# Sheet0_Top.net
KiCad netlist of a schematic drawn in Altium Designer
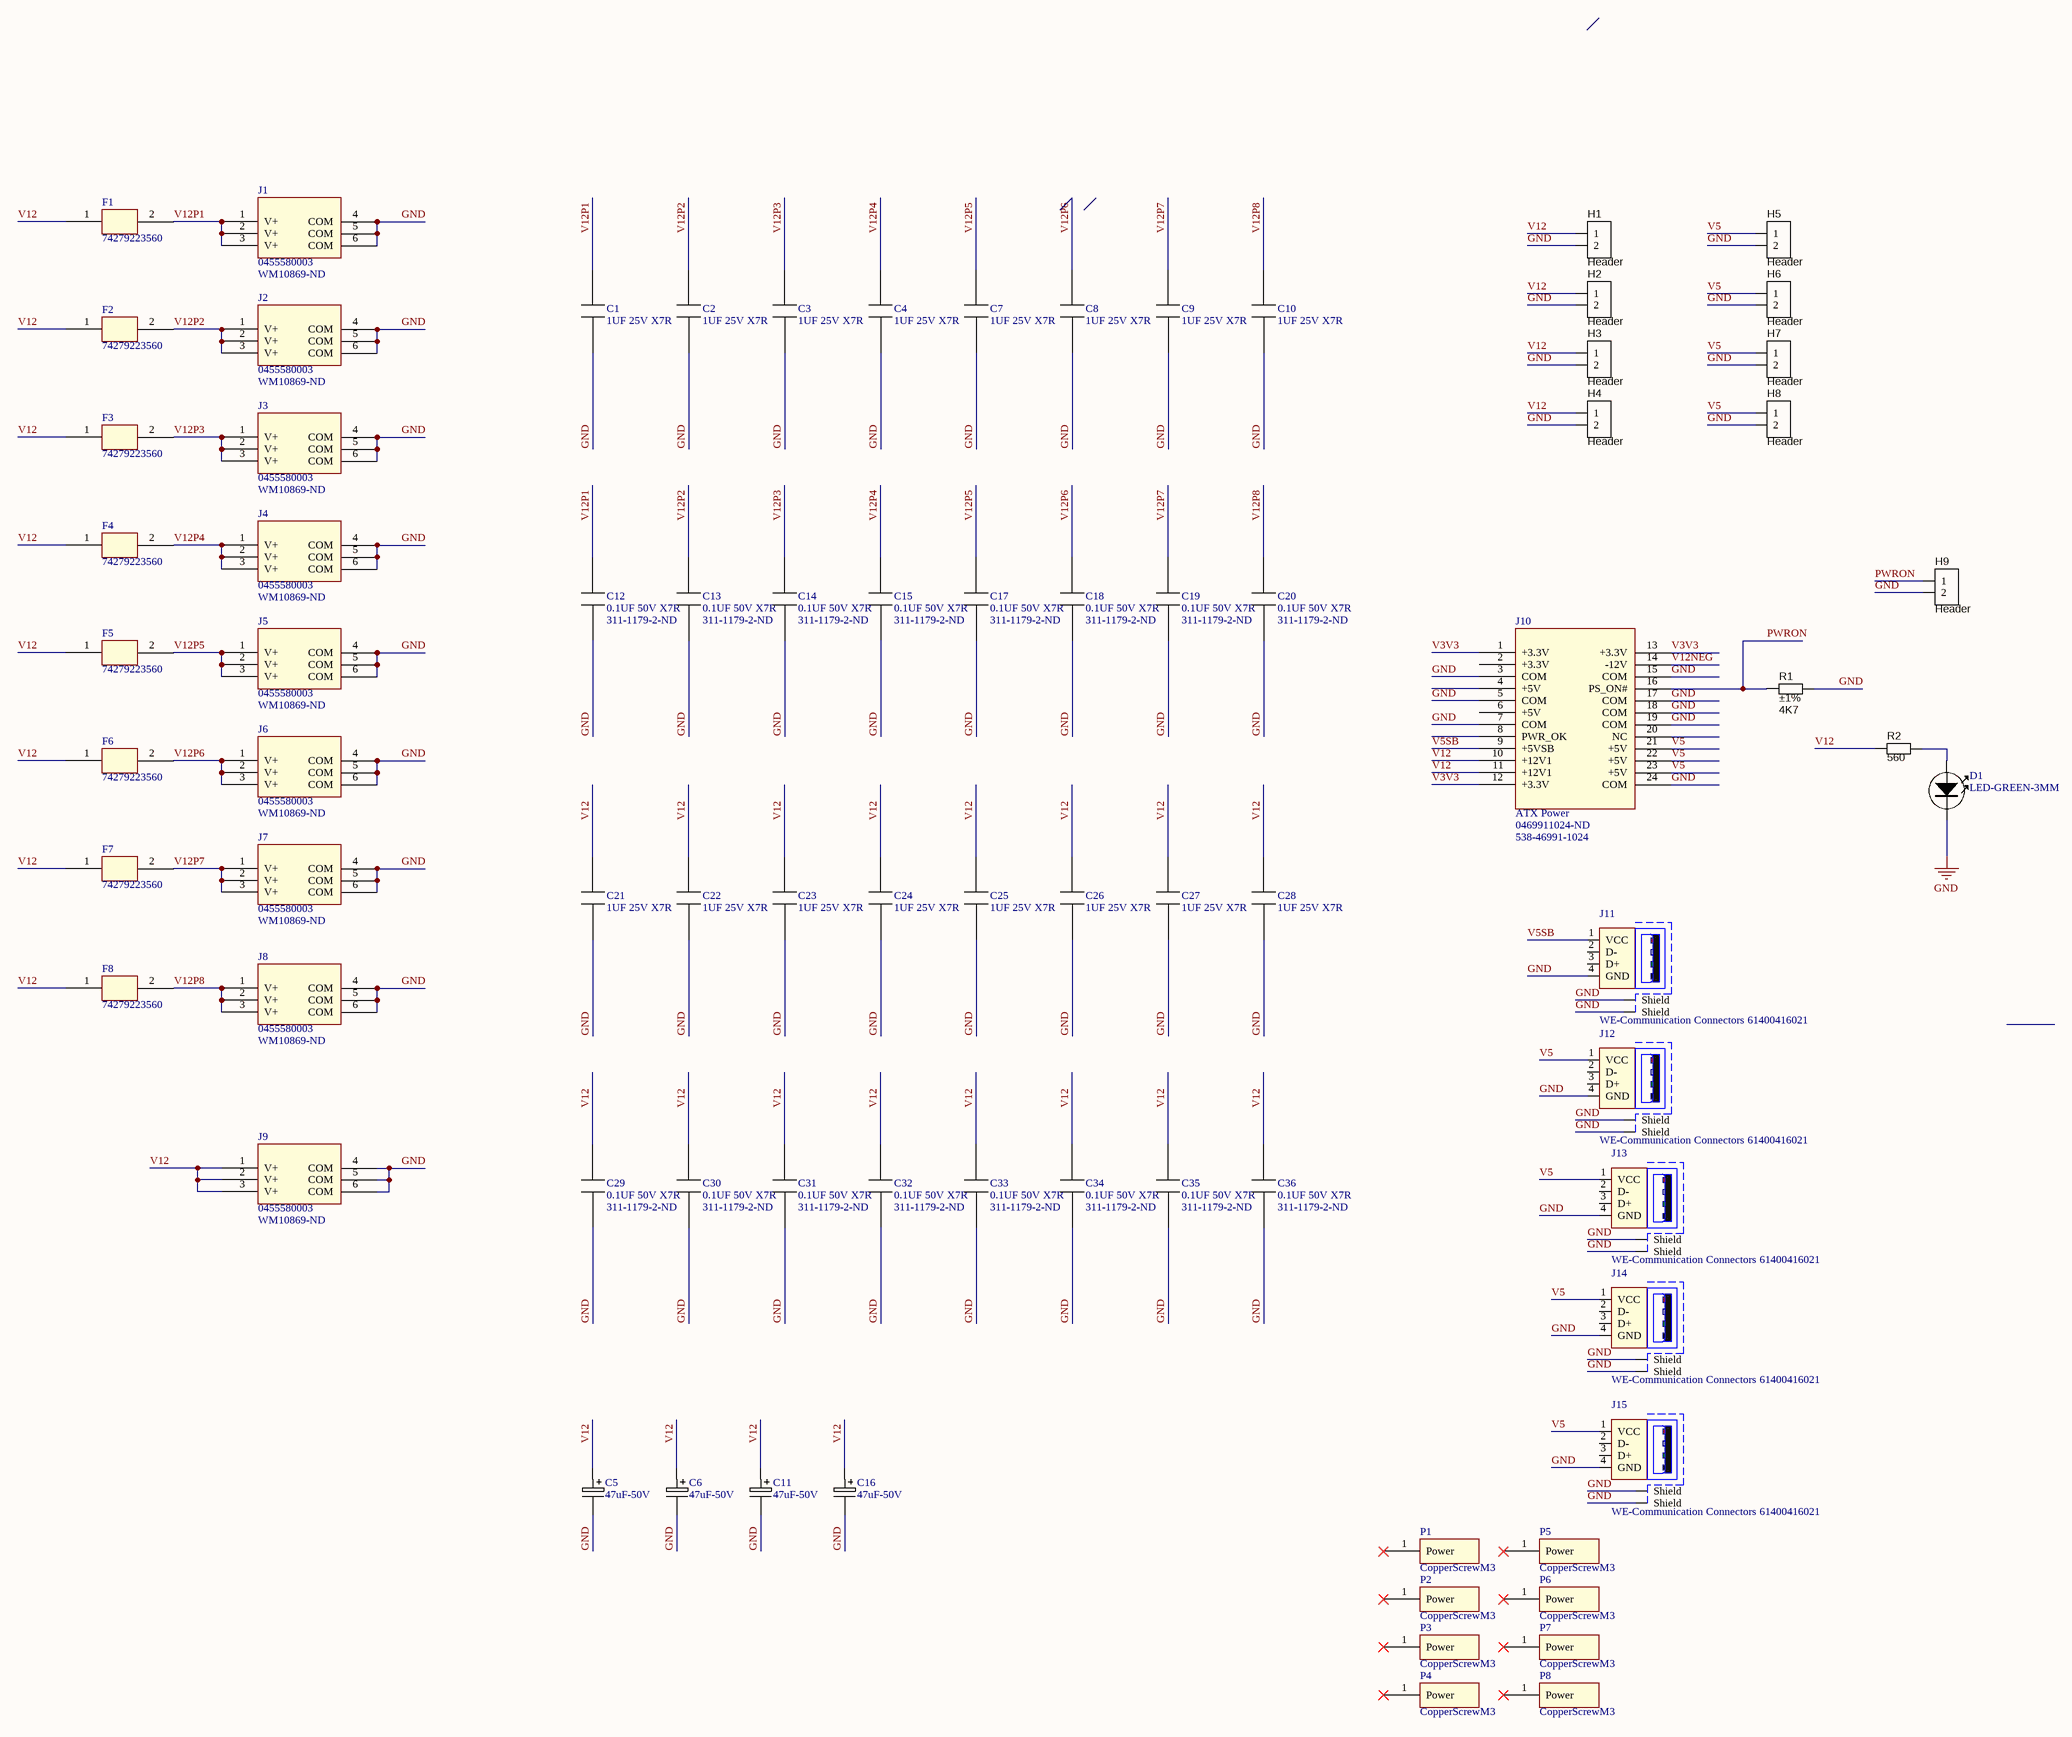
[diagram p0: Sheet0_Top.SchDoc]

(export (version "E")
  (design (tool "Eeschema 10.0.6"))
  (components
    (comp (ref "C1")
      (value "1UF 25V X7R")
      (footprint "C1206YageoX7R")
      (description "CAP CER 1UF 25V X7R 1206 Yageo CC1206KKX7R8BB105")
      (libsource (lib "servo") (part "CC1206KKX7R8BB105"))
    )
    (comp (ref "C2")
      (value "1UF 25V X7R")
      (footprint "C1206YageoX7R")
      (description "CAP CER 1UF 25V X7R 1206 Yageo CC1206KKX7R8BB105")
      (libsource (lib "servo") (part "CC1206KKX7R8BB105"))
    )
    (comp (ref "C3")
      (value "1UF 25V X7R")
      (footprint "C1206YageoX7R")
      (description "CAP CER 1UF 25V X7R 1206 Yageo CC1206KKX7R8BB105")
      (libsource (lib "servo") (part "CC1206KKX7R8BB105"))
    )
    (comp (ref "C4")
      (value "1UF 25V X7R")
      (footprint "C1206YageoX7R")
      (description "CAP CER 1UF 25V X7R 1206 Yageo CC1206KKX7R8BB105")
      (libsource (lib "servo") (part "CC1206KKX7R8BB105"))
    )
    (comp (ref "C5")
      (value "47uF-50V")
      (footprint "PANACAP-E-GENERIC")
      (description "GENERIC CAPACITOR POLARISED")
      (libsource (lib "SMD Capacitors Electrolytic") (part "PANACAP-47UF-50V-FK"))
    )
    (comp (ref "C6")
      (value "47uF-50V")
      (footprint "PANACAP-E-GENERIC")
      (description "GENERIC CAPACITOR POLARISED")
      (libsource (lib "SMD Capacitors Electrolytic") (part "PANACAP-47UF-50V-FK"))
    )
    (comp (ref "C7")
      (value "1UF 25V X7R")
      (footprint "C1206YageoX7R")
      (description "CAP CER 1UF 25V X7R 1206 Yageo CC1206KKX7R8BB105")
      (libsource (lib "servo") (part "CC1206KKX7R8BB105"))
    )
    (comp (ref "C8")
      (value "1UF 25V X7R")
      (footprint "C1206YageoX7R")
      (description "CAP CER 1UF 25V X7R 1206 Yageo CC1206KKX7R8BB105")
      (libsource (lib "servo") (part "CC1206KKX7R8BB105"))
    )
    (comp (ref "C9")
      (value "1UF 25V X7R")
      (footprint "C1206YageoX7R")
      (description "CAP CER 1UF 25V X7R 1206 Yageo CC1206KKX7R8BB105")
      (libsource (lib "servo") (part "CC1206KKX7R8BB105"))
    )
    (comp (ref "C10")
      (value "1UF 25V X7R")
      (footprint "C1206YageoX7R")
      (description "CAP CER 1UF 25V X7R 1206 Yageo CC1206KKX7R8BB105")
      (libsource (lib "servo") (part "CC1206KKX7R8BB105"))
    )
    (comp (ref "C11")
      (value "47uF-50V")
      (footprint "PANACAP-E-GENERIC")
      (description "GENERIC CAPACITOR POLARISED")
      (libsource (lib "SMD Capacitors Electrolytic") (part "PANACAP-47UF-50V-FK"))
    )
    (comp (ref "C12")
      (value "0.1UF 50V X7R")
      (footprint "C1206YageoX7R")
      (description "CAP CER 0.1UF 50V X7R 1206 YAGEO CC1206KRX7R9BB104")
      (fields (field (name "SUPPLIER PART NUMBER 1") "311-1179-2-ND"))
      (libsource (lib "servo") (part "CC1206KRX7R9BB104"))
    )
    (comp (ref "C13")
      (value "0.1UF 50V X7R")
      (footprint "C1206YageoX7R")
      (description "CAP CER 0.1UF 50V X7R 1206 YAGEO CC1206KRX7R9BB104")
      (fields (field (name "SUPPLIER PART NUMBER 1") "311-1179-2-ND"))
      (libsource (lib "servo") (part "CC1206KRX7R9BB104"))
    )
    (comp (ref "C14")
      (value "0.1UF 50V X7R")
      (footprint "C1206YageoX7R")
      (description "CAP CER 0.1UF 50V X7R 1206 YAGEO CC1206KRX7R9BB104")
      (fields (field (name "SUPPLIER PART NUMBER 1") "311-1179-2-ND"))
      (libsource (lib "servo") (part "CC1206KRX7R9BB104"))
    )
    (comp (ref "C15")
      (value "0.1UF 50V X7R")
      (footprint "C1206YageoX7R")
      (description "CAP CER 0.1UF 50V X7R 1206 YAGEO CC1206KRX7R9BB104")
      (fields (field (name "SUPPLIER PART NUMBER 1") "311-1179-2-ND"))
      (libsource (lib "servo") (part "CC1206KRX7R9BB104"))
    )
    (comp (ref "C16")
      (value "47uF-50V")
      (footprint "PANACAP-E-GENERIC")
      (description "GENERIC CAPACITOR POLARISED")
      (libsource (lib "SMD Capacitors Electrolytic") (part "PANACAP-47UF-50V-FK"))
    )
    (comp (ref "C17")
      (value "0.1UF 50V X7R")
      (footprint "C1206YageoX7R")
      (description "CAP CER 0.1UF 50V X7R 1206 YAGEO CC1206KRX7R9BB104")
      (fields (field (name "SUPPLIER PART NUMBER 1") "311-1179-2-ND"))
      (libsource (lib "servo") (part "CC1206KRX7R9BB104"))
    )
    (comp (ref "C18")
      (value "0.1UF 50V X7R")
      (footprint "C1206YageoX7R")
      (description "CAP CER 0.1UF 50V X7R 1206 YAGEO CC1206KRX7R9BB104")
      (fields (field (name "SUPPLIER PART NUMBER 1") "311-1179-2-ND"))
      (libsource (lib "servo") (part "CC1206KRX7R9BB104"))
    )
    (comp (ref "C19")
      (value "0.1UF 50V X7R")
      (footprint "C1206YageoX7R")
      (description "CAP CER 0.1UF 50V X7R 1206 YAGEO CC1206KRX7R9BB104")
      (fields (field (name "SUPPLIER PART NUMBER 1") "311-1179-2-ND"))
      (libsource (lib "servo") (part "CC1206KRX7R9BB104"))
    )
    (comp (ref "C20")
      (value "0.1UF 50V X7R")
      (footprint "C1206YageoX7R")
      (description "CAP CER 0.1UF 50V X7R 1206 YAGEO CC1206KRX7R9BB104")
      (fields (field (name "SUPPLIER PART NUMBER 1") "311-1179-2-ND"))
      (libsource (lib "servo") (part "CC1206KRX7R9BB104"))
    )
    (comp (ref "C21")
      (value "1UF 25V X7R")
      (footprint "C1206YageoX7R")
      (description "CAP CER 1UF 25V X7R 1206 Yageo CC1206KKX7R8BB105")
      (libsource (lib "servo") (part "CC1206KKX7R8BB105"))
    )
    (comp (ref "C22")
      (value "1UF 25V X7R")
      (footprint "C1206YageoX7R")
      (description "CAP CER 1UF 25V X7R 1206 Yageo CC1206KKX7R8BB105")
      (libsource (lib "servo") (part "CC1206KKX7R8BB105"))
    )
    (comp (ref "C23")
      (value "1UF 25V X7R")
      (footprint "C1206YageoX7R")
      (description "CAP CER 1UF 25V X7R 1206 Yageo CC1206KKX7R8BB105")
      (libsource (lib "servo") (part "CC1206KKX7R8BB105"))
    )
    (comp (ref "C24")
      (value "1UF 25V X7R")
      (footprint "C1206YageoX7R")
      (description "CAP CER 1UF 25V X7R 1206 Yageo CC1206KKX7R8BB105")
      (libsource (lib "servo") (part "CC1206KKX7R8BB105"))
    )
    (comp (ref "C25")
      (value "1UF 25V X7R")
      (footprint "C1206YageoX7R")
      (description "CAP CER 1UF 25V X7R 1206 Yageo CC1206KKX7R8BB105")
      (libsource (lib "servo") (part "CC1206KKX7R8BB105"))
    )
    (comp (ref "C26")
      (value "1UF 25V X7R")
      (footprint "C1206YageoX7R")
      (description "CAP CER 1UF 25V X7R 1206 Yageo CC1206KKX7R8BB105")
      (libsource (lib "servo") (part "CC1206KKX7R8BB105"))
    )
    (comp (ref "C27")
      (value "1UF 25V X7R")
      (footprint "C1206YageoX7R")
      (description "CAP CER 1UF 25V X7R 1206 Yageo CC1206KKX7R8BB105")
      (libsource (lib "servo") (part "CC1206KKX7R8BB105"))
    )
    (comp (ref "C28")
      (value "1UF 25V X7R")
      (footprint "C1206YageoX7R")
      (description "CAP CER 1UF 25V X7R 1206 Yageo CC1206KKX7R8BB105")
      (libsource (lib "servo") (part "CC1206KKX7R8BB105"))
    )
    (comp (ref "C29")
      (value "0.1UF 50V X7R")
      (footprint "C1206YageoX7R")
      (description "CAP CER 0.1UF 50V X7R 1206 YAGEO CC1206KRX7R9BB104")
      (fields (field (name "SUPPLIER PART NUMBER 1") "311-1179-2-ND"))
      (libsource (lib "servo") (part "CC1206KRX7R9BB104"))
    )
    (comp (ref "C30")
      (value "0.1UF 50V X7R")
      (footprint "C1206YageoX7R")
      (description "CAP CER 0.1UF 50V X7R 1206 YAGEO CC1206KRX7R9BB104")
      (fields (field (name "SUPPLIER PART NUMBER 1") "311-1179-2-ND"))
      (libsource (lib "servo") (part "CC1206KRX7R9BB104"))
    )
    (comp (ref "C31")
      (value "0.1UF 50V X7R")
      (footprint "C1206YageoX7R")
      (description "CAP CER 0.1UF 50V X7R 1206 YAGEO CC1206KRX7R9BB104")
      (fields (field (name "SUPPLIER PART NUMBER 1") "311-1179-2-ND"))
      (libsource (lib "servo") (part "CC1206KRX7R9BB104"))
    )
    (comp (ref "C32")
      (value "0.1UF 50V X7R")
      (footprint "C1206YageoX7R")
      (description "CAP CER 0.1UF 50V X7R 1206 YAGEO CC1206KRX7R9BB104")
      (fields (field (name "SUPPLIER PART NUMBER 1") "311-1179-2-ND"))
      (libsource (lib "servo") (part "CC1206KRX7R9BB104"))
    )
    (comp (ref "C33")
      (value "0.1UF 50V X7R")
      (footprint "C1206YageoX7R")
      (description "CAP CER 0.1UF 50V X7R 1206 YAGEO CC1206KRX7R9BB104")
      (fields (field (name "SUPPLIER PART NUMBER 1") "311-1179-2-ND"))
      (libsource (lib "servo") (part "CC1206KRX7R9BB104"))
    )
    (comp (ref "C34")
      (value "0.1UF 50V X7R")
      (footprint "C1206YageoX7R")
      (description "CAP CER 0.1UF 50V X7R 1206 YAGEO CC1206KRX7R9BB104")
      (fields (field (name "SUPPLIER PART NUMBER 1") "311-1179-2-ND"))
      (libsource (lib "servo") (part "CC1206KRX7R9BB104"))
    )
    (comp (ref "C35")
      (value "0.1UF 50V X7R")
      (footprint "C1206YageoX7R")
      (description "CAP CER 0.1UF 50V X7R 1206 YAGEO CC1206KRX7R9BB104")
      (fields (field (name "SUPPLIER PART NUMBER 1") "311-1179-2-ND"))
      (libsource (lib "servo") (part "CC1206KRX7R9BB104"))
    )
    (comp (ref "C36")
      (value "0.1UF 50V X7R")
      (footprint "C1206YageoX7R")
      (description "CAP CER 0.1UF 50V X7R 1206 YAGEO CC1206KRX7R9BB104")
      (fields (field (name "SUPPLIER PART NUMBER 1") "311-1179-2-ND"))
      (libsource (lib "servo") (part "CC1206KRX7R9BB104"))
    )
    (comp (ref "D1")
      (value "LED-GREEN-3MM")
      (footprint "LED-3MM-GREEN")
      (libsource (lib "TH Optoelectronics") (part "LED-GREEN-3MM"))
    )
    (comp (ref "F1")
      (value "74279223560")
      (footprint "74279223560")
      (description "Wurth 74279223560 Ferrite Bead 4000 uohm 10Amps")
      (libsource (lib "pwr8") (part "74279223560"))
    )
    (comp (ref "F2")
      (value "74279223560")
      (footprint "74279223560")
      (description "Wurth 74279223560 Ferrite Bead 4000 uohm 10Amps")
      (libsource (lib "pwr8") (part "74279223560"))
    )
    (comp (ref "F3")
      (value "74279223560")
      (footprint "74279223560")
      (description "Wurth 74279223560 Ferrite Bead 4000 uohm 10Amps")
      (libsource (lib "pwr8") (part "74279223560"))
    )
    (comp (ref "F4")
      (value "74279223560")
      (footprint "74279223560")
      (description "Wurth 74279223560 Ferrite Bead 4000 uohm 10Amps")
      (libsource (lib "pwr8") (part "74279223560"))
    )
    (comp (ref "F5")
      (value "74279223560")
      (footprint "74279223560")
      (description "Wurth 74279223560 Ferrite Bead 4000 uohm 10Amps")
      (libsource (lib "pwr8") (part "74279223560"))
    )
    (comp (ref "F6")
      (value "74279223560")
      (footprint "74279223560")
      (description "Wurth 74279223560 Ferrite Bead 4000 uohm 10Amps")
      (libsource (lib "pwr8") (part "74279223560"))
    )
    (comp (ref "F7")
      (value "74279223560")
      (footprint "74279223560")
      (description "Wurth 74279223560 Ferrite Bead 4000 uohm 10Amps")
      (libsource (lib "pwr8") (part "74279223560"))
    )
    (comp (ref "F8")
      (value "74279223560")
      (footprint "74279223560")
      (description "Wurth 74279223560 Ferrite Bead 4000 uohm 10Amps")
      (libsource (lib "pwr8") (part "74279223560"))
    )
    (comp (ref "H1")
      (value "Header")
      (footprint "HDR_1x2_Offset")
      (description "Header, 2-pin")
      (libsource (lib "PBL - Connectors") (part "Header2P"))
    )
    (comp (ref "H2")
      (value "Header")
      (footprint "HDR_1x2_Offset")
      (description "Header, 2-pin")
      (libsource (lib "PBL - Connectors") (part "Header2P"))
    )
    (comp (ref "H3")
      (value "Header")
      (footprint "HDR_1x2_Offset")
      (description "Header, 2-pin")
      (libsource (lib "PBL - Connectors") (part "Header2P"))
    )
    (comp (ref "H4")
      (value "Header")
      (footprint "HDR_1x2_Offset")
      (description "Header, 2-pin")
      (libsource (lib "PBL - Connectors") (part "Header2P"))
    )
    (comp (ref "H5")
      (value "Header")
      (footprint "HDR_1x2_Offset")
      (description "Header, 2-pin")
      (libsource (lib "PBL - Connectors") (part "Header2P"))
    )
    (comp (ref "H6")
      (value "Header")
      (footprint "HDR_1x2_Offset")
      (description "Header, 2-pin")
      (libsource (lib "PBL - Connectors") (part "Header2P"))
    )
    (comp (ref "H7")
      (value "Header")
      (footprint "HDR_1x2_Offset")
      (description "Header, 2-pin")
      (libsource (lib "PBL - Connectors") (part "Header2P"))
    )
    (comp (ref "H8")
      (value "Header")
      (footprint "HDR_1x2_Offset")
      (description "Header, 2-pin")
      (libsource (lib "PBL - Connectors") (part "Header2P"))
    )
    (comp (ref "H9")
      (value "Header")
      (footprint "HDR_1x2_Offset")
      (description "Header, 2-pin")
      (libsource (lib "PBL - Connectors") (part "Header2P"))
    )
    (comp (ref "J1")
      (value "0455580003")
      (footprint "45558")
      (fields (field (name "SUPPLIER PART NUMBER 1") "WM10869-ND"))
      (libsource (lib "fastcar") (part "0455580003"))
    )
    (comp (ref "J2")
      (value "0455580003")
      (footprint "45558")
      (fields (field (name "SUPPLIER PART NUMBER 1") "WM10869-ND"))
      (libsource (lib "fastcar") (part "0455580003"))
    )
    (comp (ref "J3")
      (value "0455580003")
      (footprint "45558")
      (fields (field (name "SUPPLIER PART NUMBER 1") "WM10869-ND"))
      (libsource (lib "fastcar") (part "0455580003"))
    )
    (comp (ref "J4")
      (value "0455580003")
      (footprint "45558")
      (fields (field (name "SUPPLIER PART NUMBER 1") "WM10869-ND"))
      (libsource (lib "fastcar") (part "0455580003"))
    )
    (comp (ref "J5")
      (value "0455580003")
      (footprint "45558")
      (fields (field (name "SUPPLIER PART NUMBER 1") "WM10869-ND"))
      (libsource (lib "fastcar") (part "0455580003"))
    )
    (comp (ref "J6")
      (value "0455580003")
      (footprint "45558")
      (fields (field (name "SUPPLIER PART NUMBER 1") "WM10869-ND"))
      (libsource (lib "fastcar") (part "0455580003"))
    )
    (comp (ref "J7")
      (value "0455580003")
      (footprint "45558")
      (fields (field (name "SUPPLIER PART NUMBER 1") "WM10869-ND"))
      (libsource (lib "fastcar") (part "0455580003"))
    )
    (comp (ref "J8")
      (value "0455580003")
      (footprint "45558")
      (fields (field (name "SUPPLIER PART NUMBER 1") "WM10869-ND"))
      (libsource (lib "fastcar") (part "0455580003"))
    )
    (comp (ref "J9")
      (value "0455580003")
      (footprint "45558")
      (fields (field (name "SUPPLIER PART NUMBER 1") "WM10869-ND"))
      (libsource (lib "fastcar") (part "0455580003"))
    )
    (comp (ref "J10")
      (value "ATX Power")
      (footprint "46991-1024")
      (description "Mini-Fit JR LCP RA HDR NOPEG 24C")
      (fields
        (field (name "SUPPLIER PART NUMBER 1") "0469911024-ND")
        (field (name "SUPPLIER PART NUMBER 2") "538-46991-1024")
      )
      (libsource (lib "fastcar") (part "46991-2024"))
    )
    (comp (ref "J11")
      (value "WE-Communication Connectors 61400416021")
      (footprint "61400416021")
      (description "WR-COM USB RA Type A")
      (fields
        (field (name "MANUFACTURER") "Würth Elektronik eiSos GmbH")
        (field (name "PARTNO") "61400416021")
        (field (name "CREATED BY") "Karrer Zheng")
      )
      (libsource (lib "USB-Mini_USB-Micro_USB") (part "WE-Communication Connectors 61400416021"))
    )
    (comp (ref "J12")
      (value "WE-Communication Connectors 61400416021")
      (footprint "61400416021")
      (description "WR-COM USB RA Type A")
      (fields
        (field (name "MANUFACTURER") "Würth Elektronik eiSos GmbH")
        (field (name "PARTNO") "61400416021")
        (field (name "CREATED BY") "Karrer Zheng")
      )
      (libsource (lib "USB-Mini_USB-Micro_USB") (part "WE-Communication Connectors 61400416021"))
    )
    (comp (ref "J13")
      (value "WE-Communication Connectors 61400416021")
      (footprint "61400416021")
      (description "WR-COM USB RA Type A")
      (fields
        (field (name "MANUFACTURER") "Würth Elektronik eiSos GmbH")
        (field (name "PARTNO") "61400416021")
        (field (name "CREATED BY") "Karrer Zheng")
      )
      (libsource (lib "USB-Mini_USB-Micro_USB") (part "WE-Communication Connectors 61400416021"))
    )
    (comp (ref "J14")
      (value "WE-Communication Connectors 61400416021")
      (footprint "61400416021")
      (description "WR-COM USB RA Type A")
      (fields
        (field (name "MANUFACTURER") "Würth Elektronik eiSos GmbH")
        (field (name "PARTNO") "61400416021")
        (field (name "CREATED BY") "Karrer Zheng")
      )
      (libsource (lib "USB-Mini_USB-Micro_USB") (part "WE-Communication Connectors 61400416021"))
    )
    (comp (ref "J15")
      (value "WE-Communication Connectors 61400416021")
      (footprint "61400416021")
      (description "WR-COM USB RA Type A")
      (fields
        (field (name "MANUFACTURER") "Würth Elektronik eiSos GmbH")
        (field (name "PARTNO") "61400416021")
        (field (name "CREATED BY") "Karrer Zheng")
      )
      (libsource (lib "USB-Mini_USB-Micro_USB") (part "WE-Communication Connectors 61400416021"))
    )
    (comp (ref "P1")
      (value "CopperScrewM3")
      (footprint "M3Screw")
      (libsource (lib "fastcar") (part "CopperScrewM3"))
    )
    (comp (ref "P2")
      (value "CopperScrewM3")
      (footprint "M3Screw")
      (libsource (lib "fastcar") (part "CopperScrewM3"))
    )
    (comp (ref "P3")
      (value "CopperScrewM3")
      (footprint "M3Screw")
      (libsource (lib "fastcar") (part "CopperScrewM3"))
    )
    (comp (ref "P4")
      (value "CopperScrewM3")
      (footprint "M3Screw")
      (libsource (lib "fastcar") (part "CopperScrewM3"))
    )
    (comp (ref "P5")
      (value "CopperScrewM3")
      (footprint "M3Screw")
      (libsource (lib "fastcar") (part "CopperScrewM3"))
    )
    (comp (ref "P6")
      (value "CopperScrewM3")
      (footprint "M3Screw")
      (libsource (lib "fastcar") (part "CopperScrewM3"))
    )
    (comp (ref "P7")
      (value "CopperScrewM3")
      (footprint "M3Screw")
      (libsource (lib "fastcar") (part "CopperScrewM3"))
    )
    (comp (ref "P8")
      (value "CopperScrewM3")
      (footprint "M3Screw")
      (libsource (lib "fastcar") (part "CopperScrewM3"))
    )
    (comp (ref "R1")
      (value "4K7")
      (footprint "RESC1005X40N")
      (description "Resistor SMD chip 4.7K Ohm 0.1W 1% 0402")
      (fields
        (field (name "MANUFACTURER") "Yageo")
        (field (name "MANUFACTURER PART NUMBER") "RC0603FR-074K7L")
        (field (name "TOLERANCE") "±1%")
      )
      (libsource (lib "PBL - Resistors") (part "RES_4K7_0402_1%"))
    )
    (comp (ref "R2")
      (value "560")
      (footprint "RESC3216X70N")
      (description "Resistor, SMD chip RC1206JR-07560RL RES SMD 560 OHM 5% 1/4W 1206")
      (fields (field (name "Comment") "560 Ohm .25 1206"))
      (libsource (lib "pwr8") (part "RC1206JR-07560RL"))
    )
  )
  (nets
    (net (code "1") (name "/PWRON") (class "Default")
      (node (ref "H9") (pin "1") (pinfunction "1_1") (pintype "passive"))
      (node (ref "J10") (pin "16") (pinfunction "PS_ON#_16") (pintype "passive"))
      (node (ref "R1") (pin "1") (pinfunction "1_1") (pintype "passive"))
    )
    (net (code "2") (name "/V3V3") (class "Default")
      (node (ref "J10") (pin "1") (pinfunction "+3.3V_1") (pintype "power_in"))
      (node (ref "J10") (pin "12") (pinfunction "+3.3V_12") (pintype "passive"))
      (node (ref "J10") (pin "13") (pinfunction "+3.3V_13") (pintype "passive"))
    )
    (net (code "3") (name "/V5") (class "Default")
      (node (ref "H5") (pin "1") (pinfunction "1_1") (pintype "passive"))
      (node (ref "H6") (pin "1") (pinfunction "1_1") (pintype "passive"))
      (node (ref "H7") (pin "1") (pinfunction "1_1") (pintype "passive"))
      (node (ref "H8") (pin "1") (pinfunction "1_1") (pintype "passive"))
      (node (ref "J10") (pin "21") (pinfunction "+5V_21") (pintype "passive"))
      (node (ref "J10") (pin "22") (pinfunction "+5V_22") (pintype "power_in"))
      (node (ref "J10") (pin "23") (pinfunction "+5V_23") (pintype "power_in"))
      (node (ref "J12") (pin "1") (pinfunction "VCC_1") (pintype "passive"))
      (node (ref "J13") (pin "1") (pinfunction "VCC_1") (pintype "passive"))
      (node (ref "J14") (pin "1") (pinfunction "VCC_1") (pintype "passive"))
      (node (ref "J15") (pin "1") (pinfunction "VCC_1") (pintype "passive"))
    )
    (net (code "4") (name "/V5SB") (class "Default")
      (node (ref "J10") (pin "9") (pinfunction "+5VSB_9") (pintype "passive"))
      (node (ref "J11") (pin "1") (pinfunction "VCC_1") (pintype "passive"))
    )
    (net (code "5") (name "/V12") (class "Default")
      (node (ref "C11") (pin "+") (pinfunction "+_+") (pintype "passive"))
      (node (ref "C16") (pin "+") (pinfunction "+_+") (pintype "passive"))
      (node (ref "C21") (pin "1") (pintype "passive"))
      (node (ref "C22") (pin "1") (pintype "passive"))
      (node (ref "C23") (pin "1") (pintype "passive"))
      (node (ref "C24") (pin "1") (pintype "passive"))
      (node (ref "C25") (pin "1") (pintype "passive"))
      (node (ref "C26") (pin "1") (pintype "passive"))
      (node (ref "C27") (pin "1") (pintype "passive"))
      (node (ref "C28") (pin "1") (pintype "passive"))
      (node (ref "C29") (pin "2") (pintype "passive"))
      (node (ref "C30") (pin "2") (pintype "passive"))
      (node (ref "C31") (pin "2") (pintype "passive"))
      (node (ref "C32") (pin "2") (pintype "passive"))
      (node (ref "C33") (pin "2") (pintype "passive"))
      (node (ref "C34") (pin "2") (pintype "passive"))
      (node (ref "C35") (pin "2") (pintype "passive"))
      (node (ref "C36") (pin "2") (pintype "passive"))
      (node (ref "C5") (pin "+") (pinfunction "+_+") (pintype "passive"))
      (node (ref "C6") (pin "+") (pinfunction "+_+") (pintype "passive"))
      (node (ref "F1") (pin "1") (pinfunction "1_1") (pintype "passive"))
      (node (ref "F2") (pin "1") (pinfunction "1_1") (pintype "passive"))
      (node (ref "F3") (pin "1") (pinfunction "1_1") (pintype "passive"))
      (node (ref "F4") (pin "1") (pinfunction "1_1") (pintype "passive"))
      (node (ref "F5") (pin "1") (pinfunction "1_1") (pintype "passive"))
      (node (ref "F6") (pin "1") (pinfunction "1_1") (pintype "passive"))
      (node (ref "F7") (pin "1") (pinfunction "1_1") (pintype "passive"))
      (node (ref "F8") (pin "1") (pinfunction "1_1") (pintype "passive"))
      (node (ref "H1") (pin "1") (pinfunction "1_1") (pintype "passive"))
      (node (ref "H2") (pin "1") (pinfunction "1_1") (pintype "passive"))
      (node (ref "H3") (pin "1") (pinfunction "1_1") (pintype "passive"))
      (node (ref "H4") (pin "1") (pinfunction "1_1") (pintype "passive"))
      (node (ref "J10") (pin "10") (pinfunction "+12V1_10") (pintype "passive"))
      (node (ref "J10") (pin "11") (pinfunction "+12V1_11") (pintype "passive"))
      (node (ref "J9") (pin "1") (pinfunction "V+_1") (pintype "power_in"))
      (node (ref "J9") (pin "2") (pinfunction "V+_2") (pintype "power_in"))
      (node (ref "J9") (pin "3") (pinfunction "V+_3") (pintype "power_in"))
      (node (ref "R2") (pin "1") (pinfunction "1_1") (pintype "passive"))
    )
    (net (code "6") (name "/V12NEG") (class "Default")
      (node (ref "J10") (pin "14") (pinfunction "-12V_14") (pintype "passive"))
    )
    (net (code "7") (name "/V12P1") (class "Default")
      (node (ref "C1") (pin "1") (pintype "passive"))
      (node (ref "C12") (pin "2") (pintype "passive"))
      (node (ref "F1") (pin "2") (pinfunction "2_2") (pintype "passive"))
      (node (ref "J1") (pin "1") (pinfunction "V+_1") (pintype "power_in"))
      (node (ref "J1") (pin "2") (pinfunction "V+_2") (pintype "power_in"))
      (node (ref "J1") (pin "3") (pinfunction "V+_3") (pintype "power_in"))
    )
    (net (code "8") (name "/V12P2") (class "Default")
      (node (ref "C13") (pin "2") (pintype "passive"))
      (node (ref "C2") (pin "1") (pintype "passive"))
      (node (ref "F2") (pin "2") (pinfunction "2_2") (pintype "passive"))
      (node (ref "J2") (pin "1") (pinfunction "V+_1") (pintype "power_in"))
      (node (ref "J2") (pin "2") (pinfunction "V+_2") (pintype "power_in"))
      (node (ref "J2") (pin "3") (pinfunction "V+_3") (pintype "power_in"))
    )
    (net (code "9") (name "/V12P3") (class "Default")
      (node (ref "C14") (pin "2") (pintype "passive"))
      (node (ref "C3") (pin "1") (pintype "passive"))
      (node (ref "F3") (pin "2") (pinfunction "2_2") (pintype "passive"))
      (node (ref "J3") (pin "1") (pinfunction "V+_1") (pintype "power_in"))
      (node (ref "J3") (pin "2") (pinfunction "V+_2") (pintype "power_in"))
      (node (ref "J3") (pin "3") (pinfunction "V+_3") (pintype "power_in"))
    )
    (net (code "10") (name "/V12P4") (class "Default")
      (node (ref "C15") (pin "2") (pintype "passive"))
      (node (ref "C4") (pin "1") (pintype "passive"))
      (node (ref "F4") (pin "2") (pinfunction "2_2") (pintype "passive"))
      (node (ref "J4") (pin "1") (pinfunction "V+_1") (pintype "power_in"))
      (node (ref "J4") (pin "2") (pinfunction "V+_2") (pintype "power_in"))
      (node (ref "J4") (pin "3") (pinfunction "V+_3") (pintype "power_in"))
    )
    (net (code "11") (name "/V12P5") (class "Default")
      (node (ref "C17") (pin "2") (pintype "passive"))
      (node (ref "C7") (pin "1") (pintype "passive"))
      (node (ref "F5") (pin "2") (pinfunction "2_2") (pintype "passive"))
      (node (ref "J5") (pin "1") (pinfunction "V+_1") (pintype "power_in"))
      (node (ref "J5") (pin "2") (pinfunction "V+_2") (pintype "power_in"))
      (node (ref "J5") (pin "3") (pinfunction "V+_3") (pintype "power_in"))
    )
    (net (code "12") (name "/V12P6") (class "Default")
      (node (ref "C18") (pin "2") (pintype "passive"))
      (node (ref "C8") (pin "1") (pintype "passive"))
      (node (ref "F6") (pin "2") (pinfunction "2_2") (pintype "passive"))
      (node (ref "J6") (pin "1") (pinfunction "V+_1") (pintype "power_in"))
      (node (ref "J6") (pin "2") (pinfunction "V+_2") (pintype "power_in"))
      (node (ref "J6") (pin "3") (pinfunction "V+_3") (pintype "power_in"))
    )
    (net (code "13") (name "/V12P7") (class "Default")
      (node (ref "C19") (pin "2") (pintype "passive"))
      (node (ref "C9") (pin "1") (pintype "passive"))
      (node (ref "F7") (pin "2") (pinfunction "2_2") (pintype "passive"))
      (node (ref "J7") (pin "1") (pinfunction "V+_1") (pintype "power_in"))
      (node (ref "J7") (pin "2") (pinfunction "V+_2") (pintype "power_in"))
      (node (ref "J7") (pin "3") (pinfunction "V+_3") (pintype "power_in"))
    )
    (net (code "14") (name "/V12P8") (class "Default")
      (node (ref "C10") (pin "1") (pintype "passive"))
      (node (ref "C20") (pin "2") (pintype "passive"))
      (node (ref "F8") (pin "2") (pinfunction "2_2") (pintype "passive"))
      (node (ref "J8") (pin "1") (pinfunction "V+_1") (pintype "power_in"))
      (node (ref "J8") (pin "2") (pinfunction "V+_2") (pintype "power_in"))
      (node (ref "J8") (pin "3") (pinfunction "V+_3") (pintype "power_in"))
    )
    (net (code "15") (name "GND") (class "Default")
      (node (ref "C1") (pin "2") (pintype "passive"))
      (node (ref "C10") (pin "2") (pintype "passive"))
      (node (ref "C11") (pin "-") (pinfunction "-_-") (pintype "passive"))
      (node (ref "C12") (pin "1") (pintype "passive"))
      (node (ref "C13") (pin "1") (pintype "passive"))
      (node (ref "C14") (pin "1") (pintype "passive"))
      (node (ref "C15") (pin "1") (pintype "passive"))
      (node (ref "C16") (pin "-") (pinfunction "-_-") (pintype "passive"))
      (node (ref "C17") (pin "1") (pintype "passive"))
      (node (ref "C18") (pin "1") (pintype "passive"))
      (node (ref "C19") (pin "1") (pintype "passive"))
      (node (ref "C2") (pin "2") (pintype "passive"))
      (node (ref "C20") (pin "1") (pintype "passive"))
      (node (ref "C21") (pin "2") (pintype "passive"))
      (node (ref "C22") (pin "2") (pintype "passive"))
      (node (ref "C23") (pin "2") (pintype "passive"))
      (node (ref "C24") (pin "2") (pintype "passive"))
      (node (ref "C25") (pin "2") (pintype "passive"))
      (node (ref "C26") (pin "2") (pintype "passive"))
      (node (ref "C27") (pin "2") (pintype "passive"))
      (node (ref "C28") (pin "2") (pintype "passive"))
      (node (ref "C29") (pin "1") (pintype "passive"))
      (node (ref "C3") (pin "2") (pintype "passive"))
      (node (ref "C30") (pin "1") (pintype "passive"))
      (node (ref "C31") (pin "1") (pintype "passive"))
      (node (ref "C32") (pin "1") (pintype "passive"))
      (node (ref "C33") (pin "1") (pintype "passive"))
      (node (ref "C34") (pin "1") (pintype "passive"))
      (node (ref "C35") (pin "1") (pintype "passive"))
      (node (ref "C36") (pin "1") (pintype "passive"))
      (node (ref "C4") (pin "2") (pintype "passive"))
      (node (ref "C5") (pin "-") (pinfunction "-_-") (pintype "passive"))
      (node (ref "C6") (pin "-") (pinfunction "-_-") (pintype "passive"))
      (node (ref "C7") (pin "2") (pintype "passive"))
      (node (ref "C8") (pin "2") (pintype "passive"))
      (node (ref "C9") (pin "2") (pintype "passive"))
      (node (ref "D1") (pin "K") (pintype "passive"))
      (node (ref "H1") (pin "2") (pinfunction "2_2") (pintype "passive"))
      (node (ref "H2") (pin "2") (pinfunction "2_2") (pintype "passive"))
      (node (ref "H3") (pin "2") (pinfunction "2_2") (pintype "passive"))
      (node (ref "H4") (pin "2") (pinfunction "2_2") (pintype "passive"))
      (node (ref "H5") (pin "2") (pinfunction "2_2") (pintype "passive"))
      (node (ref "H6") (pin "2") (pinfunction "2_2") (pintype "passive"))
      (node (ref "H7") (pin "2") (pinfunction "2_2") (pintype "passive"))
      (node (ref "H8") (pin "2") (pinfunction "2_2") (pintype "passive"))
      (node (ref "H9") (pin "2") (pinfunction "2_2") (pintype "passive"))
      (node (ref "J1") (pin "4") (pinfunction "COM_4") (pintype "power_in"))
      (node (ref "J1") (pin "5") (pinfunction "COM_5") (pintype "power_in"))
      (node (ref "J1") (pin "6") (pinfunction "COM_6") (pintype "power_in"))
      (node (ref "J10") (pin "15") (pinfunction "COM_15") (pintype "power_in"))
      (node (ref "J10") (pin "17") (pinfunction "COM_17") (pintype "power_in"))
      (node (ref "J10") (pin "18") (pinfunction "COM_18") (pintype "power_in"))
      (node (ref "J10") (pin "19") (pinfunction "COM_19") (pintype "power_in"))
      (node (ref "J10") (pin "24") (pinfunction "COM_24") (pintype "power_in"))
      (node (ref "J10") (pin "3") (pinfunction "COM_3") (pintype "power_in"))
      (node (ref "J10") (pin "5") (pinfunction "COM_5") (pintype "power_in"))
      (node (ref "J10") (pin "7") (pinfunction "COM_7") (pintype "power_in"))
      (node (ref "J11") (pin "4") (pinfunction "GND_4") (pintype "passive"))
      (node (ref "J11") (pin "Z1") (pinfunction "Shield_Z1") (pintype "passive"))
      (node (ref "J11") (pin "Z2") (pinfunction "Shield_Z2") (pintype "passive"))
      (node (ref "J12") (pin "4") (pinfunction "GND_4") (pintype "passive"))
      (node (ref "J12") (pin "Z1") (pinfunction "Shield_Z1") (pintype "passive"))
      (node (ref "J12") (pin "Z2") (pinfunction "Shield_Z2") (pintype "passive"))
      (node (ref "J13") (pin "4") (pinfunction "GND_4") (pintype "passive"))
      (node (ref "J13") (pin "Z1") (pinfunction "Shield_Z1") (pintype "passive"))
      (node (ref "J13") (pin "Z2") (pinfunction "Shield_Z2") (pintype "passive"))
      (node (ref "J14") (pin "4") (pinfunction "GND_4") (pintype "passive"))
      (node (ref "J14") (pin "Z1") (pinfunction "Shield_Z1") (pintype "passive"))
      (node (ref "J14") (pin "Z2") (pinfunction "Shield_Z2") (pintype "passive"))
      (node (ref "J15") (pin "4") (pinfunction "GND_4") (pintype "passive"))
      (node (ref "J15") (pin "Z1") (pinfunction "Shield_Z1") (pintype "passive"))
      (node (ref "J15") (pin "Z2") (pinfunction "Shield_Z2") (pintype "passive"))
      (node (ref "J2") (pin "4") (pinfunction "COM_4") (pintype "power_in"))
      (node (ref "J2") (pin "5") (pinfunction "COM_5") (pintype "power_in"))
      (node (ref "J2") (pin "6") (pinfunction "COM_6") (pintype "power_in"))
      (node (ref "J3") (pin "4") (pinfunction "COM_4") (pintype "power_in"))
      (node (ref "J3") (pin "5") (pinfunction "COM_5") (pintype "power_in"))
      (node (ref "J3") (pin "6") (pinfunction "COM_6") (pintype "power_in"))
      (node (ref "J4") (pin "4") (pinfunction "COM_4") (pintype "power_in"))
      (node (ref "J4") (pin "5") (pinfunction "COM_5") (pintype "power_in"))
      (node (ref "J4") (pin "6") (pinfunction "COM_6") (pintype "power_in"))
      (node (ref "J5") (pin "4") (pinfunction "COM_4") (pintype "power_in"))
      (node (ref "J5") (pin "5") (pinfunction "COM_5") (pintype "power_in"))
      (node (ref "J5") (pin "6") (pinfunction "COM_6") (pintype "power_in"))
      (node (ref "J6") (pin "4") (pinfunction "COM_4") (pintype "power_in"))
      (node (ref "J6") (pin "5") (pinfunction "COM_5") (pintype "power_in"))
      (node (ref "J6") (pin "6") (pinfunction "COM_6") (pintype "power_in"))
      (node (ref "J7") (pin "4") (pinfunction "COM_4") (pintype "power_in"))
      (node (ref "J7") (pin "5") (pinfunction "COM_5") (pintype "power_in"))
      (node (ref "J7") (pin "6") (pinfunction "COM_6") (pintype "power_in"))
      (node (ref "J8") (pin "4") (pinfunction "COM_4") (pintype "power_in"))
      (node (ref "J8") (pin "5") (pinfunction "COM_5") (pintype "power_in"))
      (node (ref "J8") (pin "6") (pinfunction "COM_6") (pintype "power_in"))
      (node (ref "J9") (pin "4") (pinfunction "COM_4") (pintype "power_in"))
      (node (ref "J9") (pin "5") (pinfunction "COM_5") (pintype "power_in"))
      (node (ref "J9") (pin "6") (pinfunction "COM_6") (pintype "power_in"))
      (node (ref "R1") (pin "2") (pinfunction "2_2") (pintype "passive"))
    )
    (net (code "16") (name "Net-(D1-PadA)") (class "Default")
      (node (ref "D1") (pin "A") (pintype "passive"))
      (node (ref "R2") (pin "2") (pinfunction "2_2") (pintype "passive"))
    )
    (net (code "17") (name "unconnected-(J10-+3.3V-Pad2)") (class "Default")
      (node (ref "J10") (pin "2") (pinfunction "+3.3V_2") (pintype "power_in"))
    )
    (net (code "18") (name "unconnected-(J10-+5V-Pad4)") (class "Default")
      (node (ref "J10") (pin "4") (pinfunction "+5V_4") (pintype "power_in"))
    )
    (net (code "19") (name "unconnected-(J10-+5V-Pad6)") (class "Default")
      (node (ref "J10") (pin "6") (pinfunction "+5V_6") (pintype "power_in"))
    )
    (net (code "20") (name "unconnected-(J10-NC-Pad20)") (class "Default")
      (node (ref "J10") (pin "20") (pinfunction "NC_20") (pintype "passive"))
    )
    (net (code "21") (name "unconnected-(J10-PWR_OK-Pad8)") (class "Default")
      (node (ref "J10") (pin "8") (pinfunction "PWR_OK_8") (pintype "passive"))
    )
    (net (code "22") (name "unconnected-(J11-D+-Pad3)") (class "Default")
      (node (ref "J11") (pin "3") (pinfunction "D+_3") (pintype "passive"))
    )
    (net (code "23") (name "unconnected-(J11-D--Pad2)") (class "Default")
      (node (ref "J11") (pin "2") (pinfunction "D-_2") (pintype "passive"))
    )
    (net (code "24") (name "unconnected-(J12-D+-Pad3)") (class "Default")
      (node (ref "J12") (pin "3") (pinfunction "D+_3") (pintype "passive"))
    )
    (net (code "25") (name "unconnected-(J12-D--Pad2)") (class "Default")
      (node (ref "J12") (pin "2") (pinfunction "D-_2") (pintype "passive"))
    )
    (net (code "26") (name "unconnected-(J13-D+-Pad3)") (class "Default")
      (node (ref "J13") (pin "3") (pinfunction "D+_3") (pintype "passive"))
    )
    (net (code "27") (name "unconnected-(J13-D--Pad2)") (class "Default")
      (node (ref "J13") (pin "2") (pinfunction "D-_2") (pintype "passive"))
    )
    (net (code "28") (name "unconnected-(J14-D+-Pad3)") (class "Default")
      (node (ref "J14") (pin "3") (pinfunction "D+_3") (pintype "passive"))
    )
    (net (code "29") (name "unconnected-(J14-D--Pad2)") (class "Default")
      (node (ref "J14") (pin "2") (pinfunction "D-_2") (pintype "passive"))
    )
    (net (code "30") (name "unconnected-(J15-D+-Pad3)") (class "Default")
      (node (ref "J15") (pin "3") (pinfunction "D+_3") (pintype "passive"))
    )
    (net (code "31") (name "unconnected-(J15-D--Pad2)") (class "Default")
      (node (ref "J15") (pin "2") (pinfunction "D-_2") (pintype "passive"))
    )
    (net (code "32") (name "unconnected-(P1-Power-Pad1)") (class "Default")
      (node (ref "P1") (pin "1") (pinfunction "Power_1") (pintype "passive+no_connect"))
    )
    (net (code "33") (name "unconnected-(P2-Power-Pad1)") (class "Default")
      (node (ref "P2") (pin "1") (pinfunction "Power_1") (pintype "passive+no_connect"))
    )
    (net (code "34") (name "unconnected-(P3-Power-Pad1)") (class "Default")
      (node (ref "P3") (pin "1") (pinfunction "Power_1") (pintype "passive+no_connect"))
    )
    (net (code "35") (name "unconnected-(P4-Power-Pad1)") (class "Default")
      (node (ref "P4") (pin "1") (pinfunction "Power_1") (pintype "passive+no_connect"))
    )
    (net (code "36") (name "unconnected-(P5-Power-Pad1)") (class "Default")
      (node (ref "P5") (pin "1") (pinfunction "Power_1") (pintype "passive+no_connect"))
    )
    (net (code "37") (name "unconnected-(P6-Power-Pad1)") (class "Default")
      (node (ref "P6") (pin "1") (pinfunction "Power_1") (pintype "passive+no_connect"))
    )
    (net (code "38") (name "unconnected-(P7-Power-Pad1)") (class "Default")
      (node (ref "P7") (pin "1") (pinfunction "Power_1") (pintype "passive+no_connect"))
    )
    (net (code "39") (name "unconnected-(P8-Power-Pad1)") (class "Default")
      (node (ref "P8") (pin "1") (pinfunction "Power_1") (pintype "passive+no_connect"))
    )
  )
)
